# M_C_ext_esp32.net
KiCad netlist of a schematic drawn in EAGLE
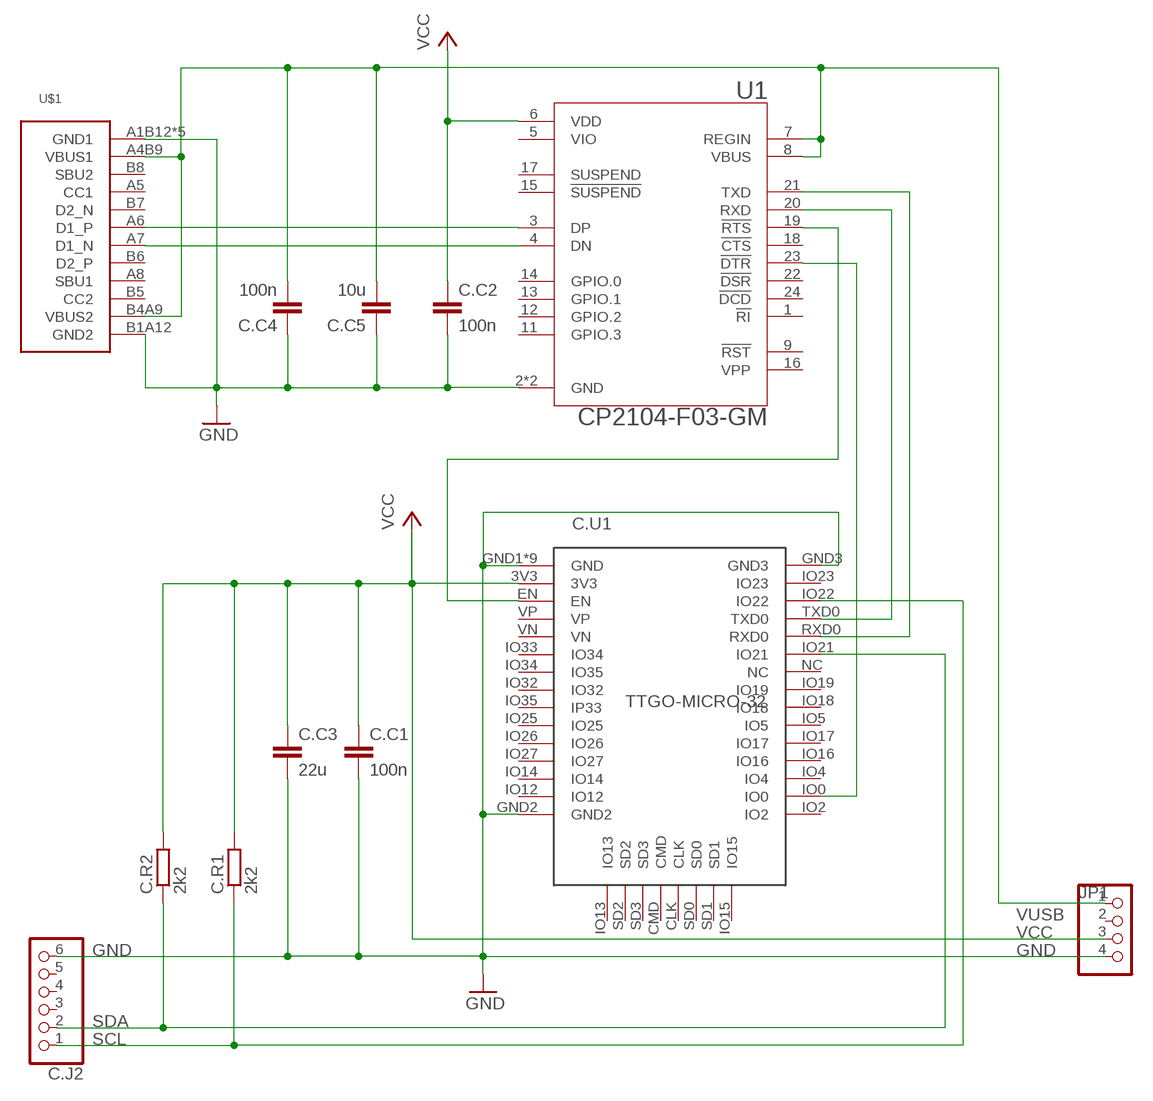
[diagram p0: schematic, sheet 1]

(export (version "E")
  (design (tool "Eeschema 10.0.6"))
  (components
    (comp (ref "C.C1")
      (value "100n")
      (footprint "eagle-import:C0603")
      (libsource (lib "eagle-import") (part "C-EUC0603"))
    )
    (comp (ref "C.C2")
      (value "100n")
      (footprint "eagle-import:C0603")
      (libsource (lib "eagle-import") (part "C-EUC0603"))
    )
    (comp (ref "C.C3")
      (value "22u")
      (footprint "eagle-import:C0805")
      (libsource (lib "eagle-import") (part "C-EUC0805"))
    )
    (comp (ref "C.C4")
      (value "100n")
      (footprint "eagle-import:C0603")
      (libsource (lib "eagle-import") (part "C-EUC0603"))
    )
    (comp (ref "C.C5")
      (value "10u")
      (footprint "eagle-import:C0603")
      (libsource (lib "eagle-import") (part "C-EUC0603"))
    )
    (comp (ref "C.J2")
      (value "PINHD-1X6")
      (footprint "eagle-import:1X06")
      (libsource (lib "eagle-import") (part "PINHD-1X6"))
    )
    (comp (ref "C.R1")
      (value "2k2")
      (footprint "eagle-import:R0603")
      (libsource (lib "eagle-import") (part "R-EU_R0603"))
    )
    (comp (ref "C.R2")
      (value "2k2")
      (footprint "eagle-import:R0603")
      (libsource (lib "eagle-import") (part "R-EU_R0603"))
    )
    (comp (ref "C.U1")
      (value "TTGO-MICRO-32")
      (footprint "eagle-import:TTGO-MICRO-32")
      (libsource (lib "eagle-import") (part "TTGO-MICRO-32"))
    )
    (comp (ref "JP1")
      (value "PINHD-1X4")
      (footprint "eagle-import:1X04")
      (libsource (lib "eagle-import") (part "PINHD-1X4"))
    )
    (comp (ref "U$1")
      (value "USB-C")
      (footprint "eagle-import:USB-C")
      (libsource (lib "eagle-import") (part "USB-C"))
    )
    (comp (ref "U1")
      (value "CP2104-F03-GM")
      (footprint "eagle-import:QFN50P400X400X80-25N")
      (fields (field (name "MF") "Silicon Labs") (field (name "MP") "CP2104"))
      (libsource (lib "eagle-import") (part "CP2104-F03-GM"))
    )
  )
  (nets
    (net (code "1") (name "/SCL") (class "Default")
      (node (ref "C.J2") (pin "1") (pinfunction "1_1") (pintype "passive"))
      (node (ref "C.R1") (pin "1") (pinfunction "1_1") (pintype "passive"))
      (node (ref "C.U1") (pin "IO22") (pinfunction "IO22_IO22") (pintype "bidirectional"))
    )
    (net (code "2") (name "/SDA") (class "Default")
      (node (ref "C.J2") (pin "2") (pinfunction "2_2") (pintype "passive"))
      (node (ref "C.R2") (pin "1") (pinfunction "1_1") (pintype "passive"))
      (node (ref "C.U1") (pin "IO21") (pinfunction "IO21_IO21") (pintype "bidirectional"))
    )
    (net (code "3") (name "/VIO") (class "Default")
      (node (ref "U1") (pin "5") (pinfunction "VIO_5") (pintype "power_in"))
    )
    (net (code "4") (name "/VUSB") (class "Default")
      (node (ref "C.C4") (pin "2") (pinfunction "2_2") (pintype "passive"))
      (node (ref "C.C5") (pin "2") (pinfunction "2_2") (pintype "passive"))
      (node (ref "JP1") (pin "1") (pinfunction "1_1") (pintype "passive"))
      (node (ref "U$1") (pin "A4B9") (pinfunction "VBUS1_A4B9") (pintype "bidirectional"))
      (node (ref "U$1") (pin "B4A9") (pinfunction "VBUS2_B4A9") (pintype "bidirectional"))
      (node (ref "U1") (pin "7") (pinfunction "REGIN_7") (pintype "input"))
      (node (ref "U1") (pin "8") (pinfunction "VBUS_8") (pintype "input"))
    )
    (net (code "5") (name "GND") (class "Default")
      (node (ref "C.C1") (pin "2") (pinfunction "2_2") (pintype "passive"))
      (node (ref "C.C2") (pin "2") (pinfunction "2_2") (pintype "passive"))
      (node (ref "C.C3") (pin "2") (pinfunction "2_2") (pintype "passive"))
      (node (ref "C.C4") (pin "1") (pinfunction "1_1") (pintype "passive"))
      (node (ref "C.C5") (pin "1") (pinfunction "1_1") (pintype "passive"))
      (node (ref "C.J2") (pin "6") (pinfunction "6_6") (pintype "passive"))
      (node (ref "C.U1") (pin "GND1") (pinfunction "GND_GND1") (pintype "power_in"))
      (node (ref "C.U1") (pin "GND10") (pinfunction "GND_GND10") (pintype "power_in"))
      (node (ref "C.U1") (pin "GND11") (pinfunction "GND_GND11") (pintype "power_in"))
      (node (ref "C.U1") (pin "GND2") (pinfunction "GND2_GND2") (pintype "power_in"))
      (node (ref "C.U1") (pin "GND3") (pinfunction "GND3_GND3") (pintype "power_in"))
      (node (ref "C.U1") (pin "GND4") (pinfunction "GND_GND4") (pintype "power_in"))
      (node (ref "C.U1") (pin "GND5") (pinfunction "GND_GND5") (pintype "power_in"))
      (node (ref "C.U1") (pin "GND6") (pinfunction "GND_GND6") (pintype "power_in"))
      (node (ref "C.U1") (pin "GND7") (pinfunction "GND_GND7") (pintype "power_in"))
      (node (ref "C.U1") (pin "GND8") (pinfunction "GND_GND8") (pintype "power_in"))
      (node (ref "C.U1") (pin "GND9") (pinfunction "GND_GND9") (pintype "power_in"))
      (node (ref "JP1") (pin "4") (pinfunction "4_4") (pintype "passive"))
      (node (ref "U$1") (pin "A1B12") (pinfunction "GND1_A1B12") (pintype "bidirectional"))
      (node (ref "U$1") (pin "B1A12") (pinfunction "GND2_B1A12") (pintype "bidirectional"))
      (node (ref "U$1") (pin "SH1") (pinfunction "GND1_SH1") (pintype "bidirectional"))
      (node (ref "U$1") (pin "SH2") (pinfunction "GND1_SH2") (pintype "bidirectional"))
      (node (ref "U$1") (pin "SH3") (pinfunction "GND1_SH3") (pintype "bidirectional"))
      (node (ref "U$1") (pin "SH4") (pinfunction "GND1_SH4") (pintype "bidirectional"))
      (node (ref "U1") (pin "2") (pinfunction "GND_2") (pintype "power_in"))
      (node (ref "U1") (pin "25") (pinfunction "GND_25") (pintype "power_in"))
    )
    (net (code "6") (name "Net-(U$1-D1_N)") (class "Default")
      (node (ref "U$1") (pin "A7") (pinfunction "D1_N_A7") (pintype "bidirectional"))
      (node (ref "U1") (pin "4") (pinfunction "DN_4") (pintype "bidirectional"))
    )
    (net (code "7") (name "Net-(U$1-D1_P)") (class "Default")
      (node (ref "U$1") (pin "A6") (pinfunction "D1_P_A6") (pintype "bidirectional"))
      (node (ref "U1") (pin "3") (pinfunction "DP_3") (pintype "bidirectional"))
    )
    (net (code "8") (name "Net-(U1-RXD)") (class "Default")
      (node (ref "C.U1") (pin "TXD0") (pinfunction "TXD0_TXD0") (pintype "bidirectional"))
      (node (ref "U1") (pin "20") (pinfunction "RXD_20") (pintype "input"))
    )
    (net (code "9") (name "Net-(U1-TXD)") (class "Default")
      (node (ref "C.U1") (pin "RXD0") (pinfunction "RXD0_RXD0") (pintype "bidirectional"))
      (node (ref "U1") (pin "21") (pinfunction "TXD_21") (pintype "output"))
    )
    (net (code "10") (name "Net-(U1-~{DTR})") (class "Default")
      (node (ref "C.U1") (pin "IO0") (pinfunction "IO0_IO0") (pintype "bidirectional"))
      (node (ref "U1") (pin "23") (pinfunction "~{DTR}_23") (pintype "output"))
    )
    (net (code "11") (name "Net-(U1-~{RTS})") (class "Default")
      (node (ref "C.U1") (pin "EN") (pinfunction "EN_EN") (pintype "bidirectional"))
      (node (ref "U1") (pin "19") (pinfunction "~{RTS}_19") (pintype "output"))
    )
    (net (code "12") (name "VCC") (class "Default")
      (node (ref "C.C1") (pin "1") (pinfunction "1_1") (pintype "passive"))
      (node (ref "C.C2") (pin "1") (pinfunction "1_1") (pintype "passive"))
      (node (ref "C.C3") (pin "1") (pinfunction "1_1") (pintype "passive"))
      (node (ref "C.R1") (pin "2") (pinfunction "2_2") (pintype "passive"))
      (node (ref "C.R2") (pin "2") (pinfunction "2_2") (pintype "passive"))
      (node (ref "C.U1") (pin "3V3") (pinfunction "3V3_3V3") (pintype "power_in"))
      (node (ref "JP1") (pin "3") (pinfunction "3_3") (pintype "passive"))
      (node (ref "U1") (pin "6") (pinfunction "VDD_6") (pintype "power_in"))
    )
    (net (code "13") (name "unconnected-(C.J2-Pad3)") (class "Default")
      (node (ref "C.J2") (pin "3") (pinfunction "3_3") (pintype "passive"))
    )
    (net (code "14") (name "unconnected-(C.J2-Pad4)") (class "Default")
      (node (ref "C.J2") (pin "4") (pinfunction "4_4") (pintype "passive"))
    )
    (net (code "15") (name "unconnected-(C.J2-Pad5)") (class "Default")
      (node (ref "C.J2") (pin "5") (pinfunction "5_5") (pintype "passive"))
    )
    (net (code "16") (name "unconnected-(C.U1-IO34-PadIO33)") (class "Default")
      (node (ref "C.U1") (pin "IO33") (pinfunction "IO34_IO33") (pintype "bidirectional"))
    )
    (net (code "17") (name "unconnected-(C.U1-IO35-PadIO34)") (class "Default")
      (node (ref "C.U1") (pin "IO34") (pinfunction "IO35_IO34") (pintype "bidirectional"))
    )
    (net (code "18") (name "unconnected-(C.U1-IP33-PadIO35)") (class "Default")
      (node (ref "C.U1") (pin "IO35") (pinfunction "IP33_IO35") (pintype "bidirectional"))
    )
    (net (code "19") (name "unconnected-(C.U1-PadCLK)") (class "Default")
      (node (ref "C.U1") (pin "CLK") (pinfunction "CLK_CLK") (pintype "bidirectional"))
    )
    (net (code "20") (name "unconnected-(C.U1-PadCMD)") (class "Default")
      (node (ref "C.U1") (pin "CMD") (pinfunction "CMD_CMD") (pintype "bidirectional"))
    )
    (net (code "21") (name "unconnected-(C.U1-PadIO2)") (class "Default")
      (node (ref "C.U1") (pin "IO2") (pinfunction "IO2_IO2") (pintype "bidirectional"))
    )
    (net (code "22") (name "unconnected-(C.U1-PadIO4)") (class "Default")
      (node (ref "C.U1") (pin "IO4") (pinfunction "IO4_IO4") (pintype "bidirectional"))
    )
    (net (code "23") (name "unconnected-(C.U1-PadIO5)") (class "Default")
      (node (ref "C.U1") (pin "IO5") (pinfunction "IO5_IO5") (pintype "bidirectional"))
    )
    (net (code "24") (name "unconnected-(C.U1-PadIO12)") (class "Default")
      (node (ref "C.U1") (pin "IO12") (pinfunction "IO12_IO12") (pintype "bidirectional"))
    )
    (net (code "25") (name "unconnected-(C.U1-PadIO13)") (class "Default")
      (node (ref "C.U1") (pin "IO13") (pinfunction "IO13_IO13") (pintype "bidirectional"))
    )
    (net (code "26") (name "unconnected-(C.U1-PadIO14)") (class "Default")
      (node (ref "C.U1") (pin "IO14") (pinfunction "IO14_IO14") (pintype "bidirectional"))
    )
    (net (code "27") (name "unconnected-(C.U1-PadIO15)") (class "Default")
      (node (ref "C.U1") (pin "IO15") (pinfunction "IO15_IO15") (pintype "bidirectional"))
    )
    (net (code "28") (name "unconnected-(C.U1-PadIO16)") (class "Default")
      (node (ref "C.U1") (pin "IO16") (pinfunction "IO16_IO16") (pintype "bidirectional"))
    )
    (net (code "29") (name "unconnected-(C.U1-PadIO17)") (class "Default")
      (node (ref "C.U1") (pin "IO17") (pinfunction "IO17_IO17") (pintype "bidirectional"))
    )
    (net (code "30") (name "unconnected-(C.U1-PadIO18)") (class "Default")
      (node (ref "C.U1") (pin "IO18") (pinfunction "IO18_IO18") (pintype "bidirectional"))
    )
    (net (code "31") (name "unconnected-(C.U1-PadIO19)") (class "Default")
      (node (ref "C.U1") (pin "IO19") (pinfunction "IO19_IO19") (pintype "bidirectional"))
    )
    (net (code "32") (name "unconnected-(C.U1-PadIO23)") (class "Default")
      (node (ref "C.U1") (pin "IO23") (pinfunction "IO23_IO23") (pintype "bidirectional"))
    )
    (net (code "33") (name "unconnected-(C.U1-PadIO25)") (class "Default")
      (node (ref "C.U1") (pin "IO25") (pinfunction "IO25_IO25") (pintype "bidirectional"))
    )
    (net (code "34") (name "unconnected-(C.U1-PadIO26)") (class "Default")
      (node (ref "C.U1") (pin "IO26") (pinfunction "IO26_IO26") (pintype "bidirectional"))
    )
    (net (code "35") (name "unconnected-(C.U1-PadIO27)") (class "Default")
      (node (ref "C.U1") (pin "IO27") (pinfunction "IO27_IO27") (pintype "bidirectional"))
    )
    (net (code "36") (name "unconnected-(C.U1-PadIO32)") (class "Default")
      (node (ref "C.U1") (pin "IO32") (pinfunction "IO32_IO32") (pintype "bidirectional"))
    )
    (net (code "37") (name "unconnected-(C.U1-PadNC)") (class "Default")
      (node (ref "C.U1") (pin "NC") (pinfunction "NC_NC") (pintype "no_connect"))
    )
    (net (code "38") (name "unconnected-(C.U1-PadSD0)") (class "Default")
      (node (ref "C.U1") (pin "SD0") (pinfunction "SD0_SD0") (pintype "bidirectional"))
    )
    (net (code "39") (name "unconnected-(C.U1-PadSD1)") (class "Default")
      (node (ref "C.U1") (pin "SD1") (pinfunction "SD1_SD1") (pintype "bidirectional"))
    )
    (net (code "40") (name "unconnected-(C.U1-PadSD2)") (class "Default")
      (node (ref "C.U1") (pin "SD2") (pinfunction "SD2_SD2") (pintype "bidirectional"))
    )
    (net (code "41") (name "unconnected-(C.U1-PadSD3)") (class "Default")
      (node (ref "C.U1") (pin "SD3") (pinfunction "SD3_SD3") (pintype "bidirectional"))
    )
    (net (code "42") (name "unconnected-(C.U1-PadVN)") (class "Default")
      (node (ref "C.U1") (pin "VN") (pinfunction "VN_VN") (pintype "bidirectional"))
    )
    (net (code "43") (name "unconnected-(C.U1-PadVP)") (class "Default")
      (node (ref "C.U1") (pin "VP") (pinfunction "VP_VP") (pintype "bidirectional"))
    )
    (net (code "44") (name "unconnected-(JP1-Pad2)") (class "Default")
      (node (ref "JP1") (pin "2") (pinfunction "2_2") (pintype "passive"))
    )
    (net (code "45") (name "unconnected-(U$1-CC1-PadA5)") (class "Default")
      (node (ref "U$1") (pin "A5") (pinfunction "CC1_A5") (pintype "bidirectional"))
    )
    (net (code "46") (name "unconnected-(U$1-CC2-PadB5)") (class "Default")
      (node (ref "U$1") (pin "B5") (pinfunction "CC2_B5") (pintype "bidirectional"))
    )
    (net (code "47") (name "unconnected-(U$1-D2_N-PadB7)") (class "Default")
      (node (ref "U$1") (pin "B7") (pinfunction "D2_N_B7") (pintype "bidirectional"))
    )
    (net (code "48") (name "unconnected-(U$1-D2_P-PadB6)") (class "Default")
      (node (ref "U$1") (pin "B6") (pinfunction "D2_P_B6") (pintype "bidirectional"))
    )
    (net (code "49") (name "unconnected-(U$1-SBU1-PadA8)") (class "Default")
      (node (ref "U$1") (pin "A8") (pinfunction "SBU1_A8") (pintype "bidirectional"))
    )
    (net (code "50") (name "unconnected-(U$1-SBU2-PadB8)") (class "Default")
      (node (ref "U$1") (pin "B8") (pinfunction "SBU2_B8") (pintype "bidirectional"))
    )
    (net (code "51") (name "unconnected-(U1-GPIO.0-Pad14)") (class "Default")
      (node (ref "U1") (pin "14") (pinfunction "GPIO.0_14") (pintype "bidirectional"))
    )
    (net (code "52") (name "unconnected-(U1-GPIO.1-Pad13)") (class "Default")
      (node (ref "U1") (pin "13") (pinfunction "GPIO.1_13") (pintype "bidirectional"))
    )
    (net (code "53") (name "unconnected-(U1-GPIO.2-Pad12)") (class "Default")
      (node (ref "U1") (pin "12") (pinfunction "GPIO.2_12") (pintype "bidirectional"))
    )
    (net (code "54") (name "unconnected-(U1-GPIO.3-Pad11)") (class "Default")
      (node (ref "U1") (pin "11") (pinfunction "GPIO.3_11") (pintype "bidirectional"))
    )
    (net (code "55") (name "unconnected-(U1-SUSPEND-Pad17)") (class "Default")
      (node (ref "U1") (pin "17") (pinfunction "SUSPEND_17") (pintype "output"))
    )
    (net (code "56") (name "unconnected-(U1-VPP-Pad16)") (class "Default")
      (node (ref "U1") (pin "16") (pinfunction "VPP_16") (pintype "passive"))
    )
    (net (code "57") (name "unconnected-(U1-~{CTS}-Pad18)") (class "Default")
      (node (ref "U1") (pin "18") (pinfunction "~{CTS}_18") (pintype "input"))
    )
    (net (code "58") (name "unconnected-(U1-~{DCD}-Pad24)") (class "Default")
      (node (ref "U1") (pin "24") (pinfunction "~{DCD}_24") (pintype "input"))
    )
    (net (code "59") (name "unconnected-(U1-~{DSR}-Pad22)") (class "Default")
      (node (ref "U1") (pin "22") (pinfunction "~{DSR}_22") (pintype "input"))
    )
    (net (code "60") (name "unconnected-(U1-~{RI}-Pad1)") (class "Default")
      (node (ref "U1") (pin "1") (pinfunction "~{RI}_1") (pintype "input"))
    )
    (net (code "61") (name "unconnected-(U1-~{RST}-Pad9)") (class "Default")
      (node (ref "U1") (pin "9") (pinfunction "~{RST}_9") (pintype "bidirectional"))
    )
    (net (code "62") (name "unconnected-(U1-~{SUSPEND}-Pad15)") (class "Default")
      (node (ref "U1") (pin "15") (pinfunction "~{SUSPEND}_15") (pintype "output"))
    )
  )
)
